# KegWasher_1_3_Schematic_EasyEDA.net
KiCad netlist of a schematic drawn in EasyEDA
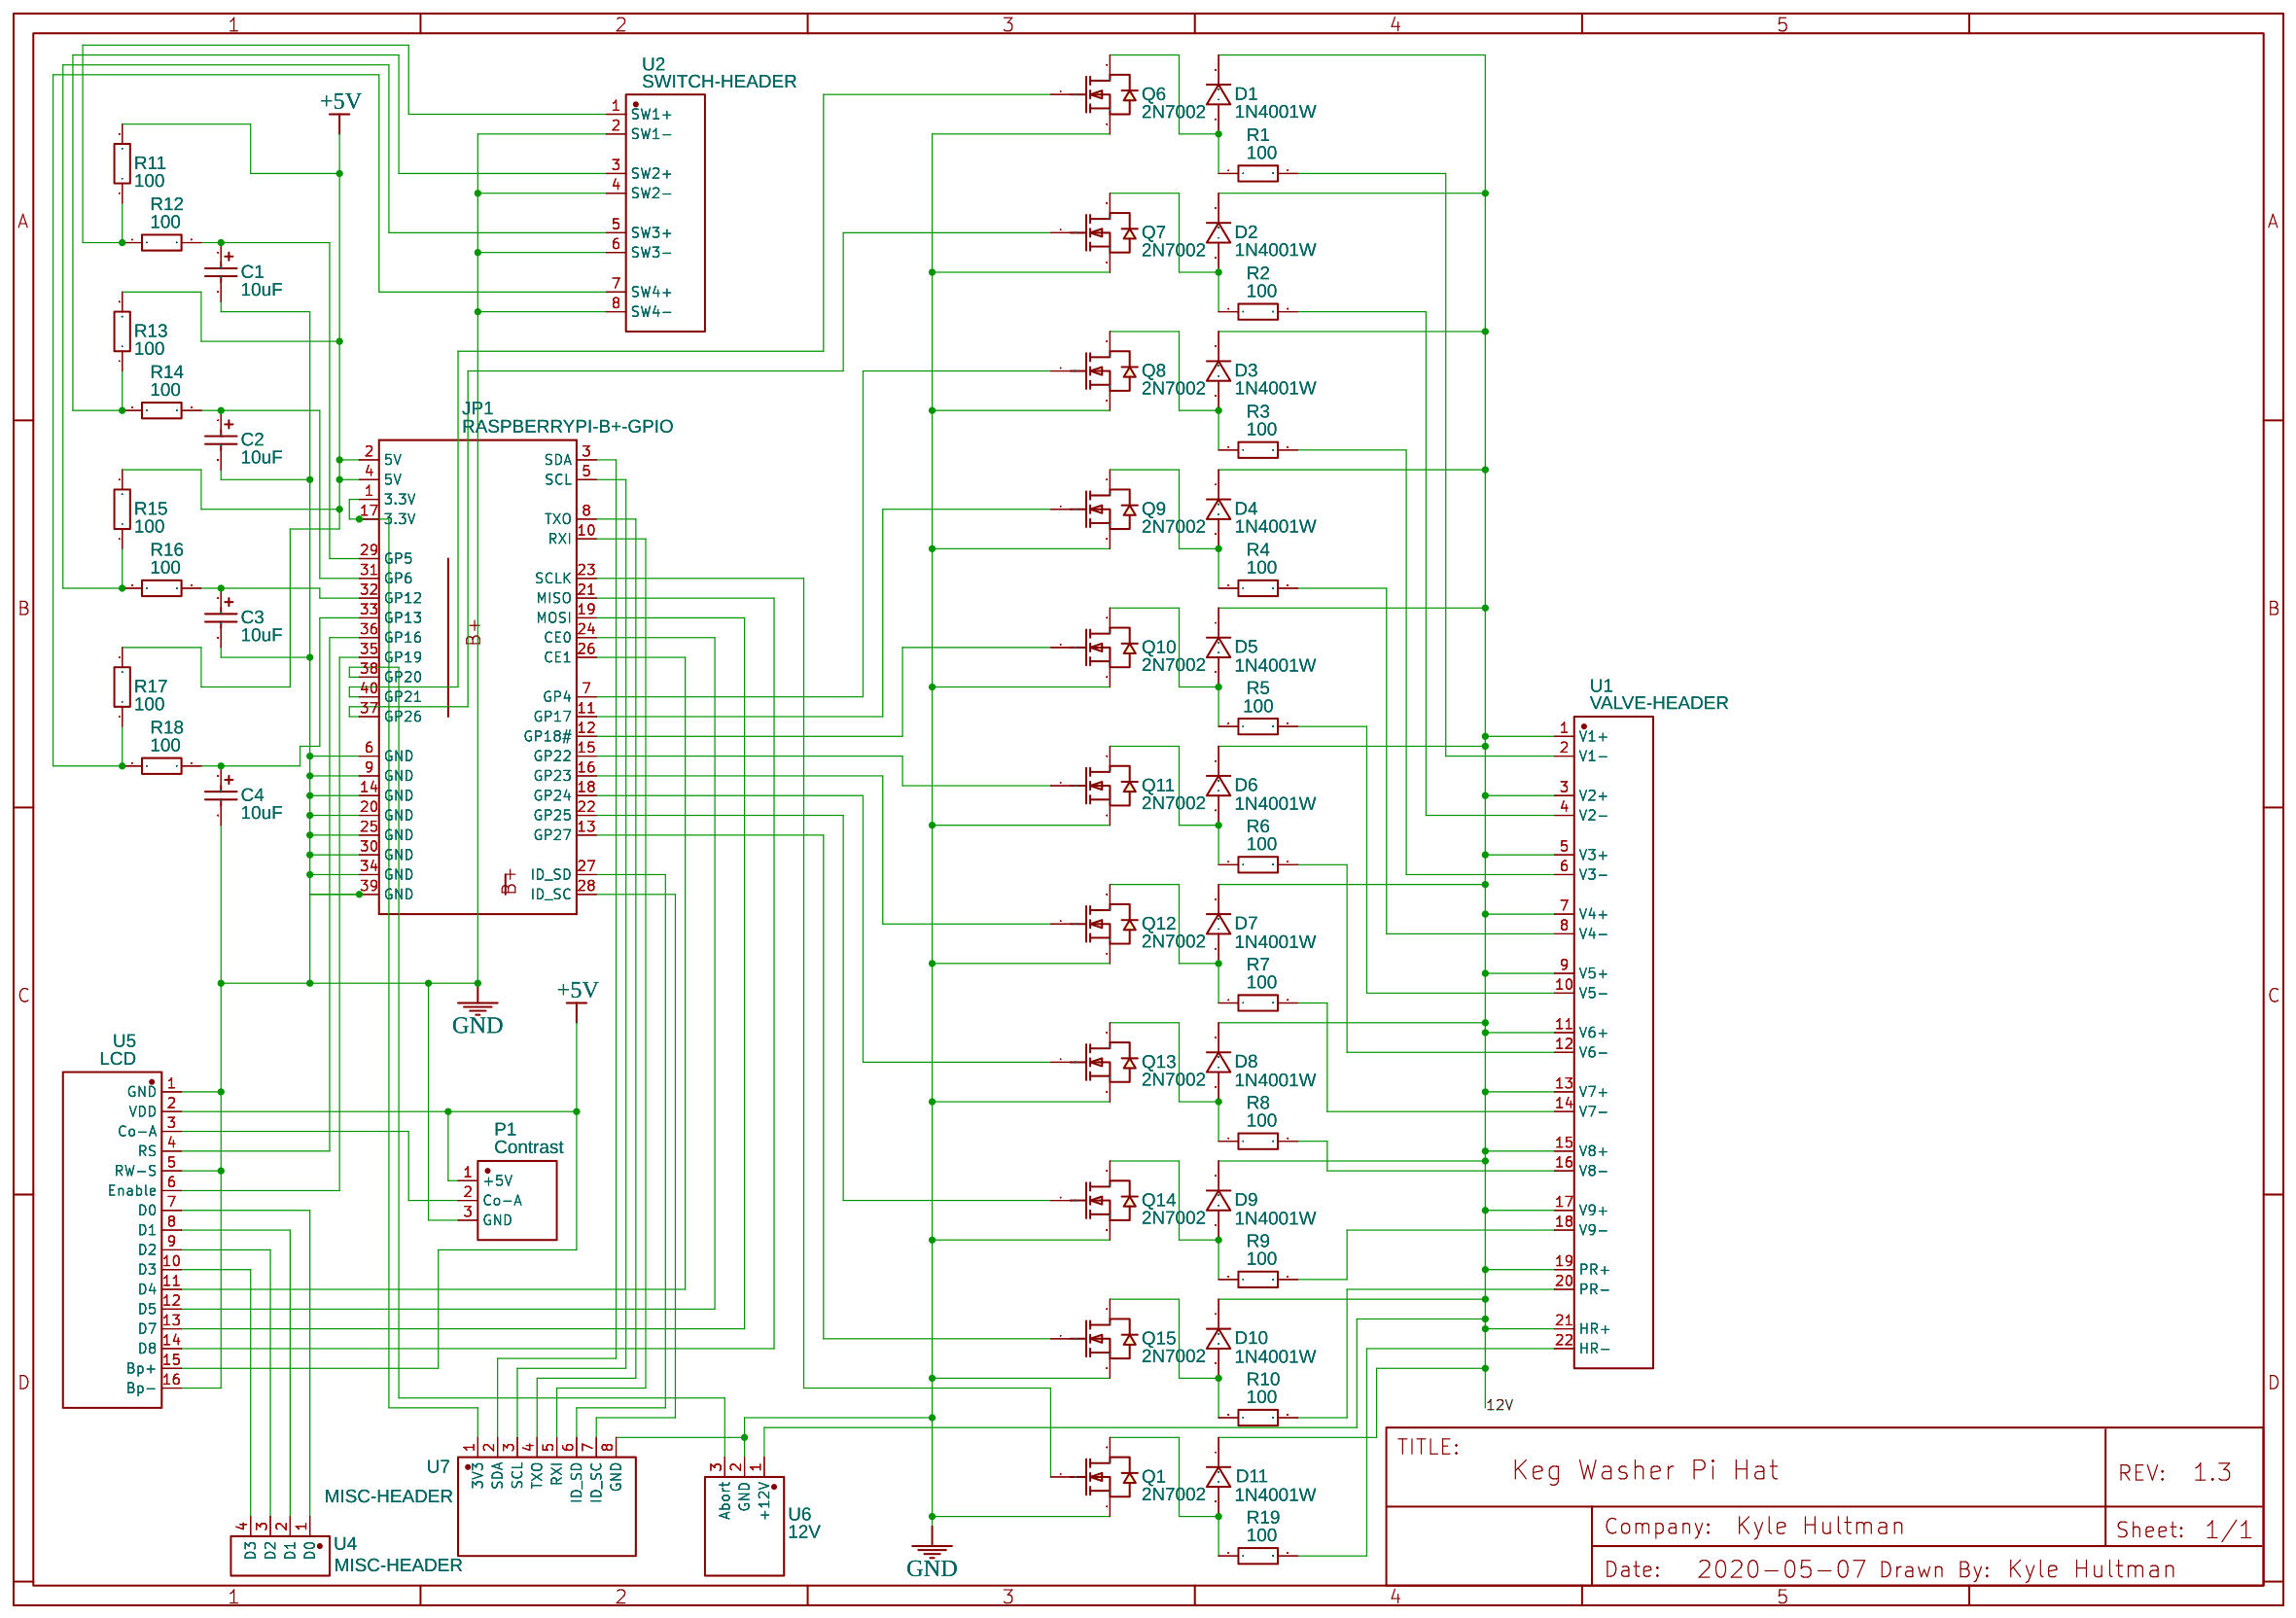
[diagram p0: schematic sheet]

(export (version "E")
  (design (tool "Eeschema 10.0.6"))
  (components
    (comp (ref "C1")
      (value "10uF")
      (fields
        (field (name "BOM_Manufacturer Part") "TAJA106K016RNJ")
        (field (name "BOM_Supplier Part") "C7171")
      )
      (libsource (lib "") (part "TAJA106K016RNJ"))
    )
    (comp (ref "C2")
      (value "10uF")
      (fields
        (field (name "BOM_Manufacturer Part") "TAJA106K016RNJ")
        (field (name "BOM_Supplier Part") "C7171")
      )
      (libsource (lib "") (part "TAJA106K016RNJ"))
    )
    (comp (ref "C3")
      (value "10uF")
      (fields
        (field (name "BOM_Manufacturer Part") "TAJA106K016RNJ")
        (field (name "BOM_Supplier Part") "C7171")
      )
      (libsource (lib "") (part "TAJA106K016RNJ"))
    )
    (comp (ref "C4")
      (value "10uF")
      (fields
        (field (name "BOM_Manufacturer Part") "TAJA106K016RNJ")
        (field (name "BOM_Supplier Part") "C7171")
      )
      (libsource (lib "") (part "TAJA106K016RNJ"))
    )
    (comp (ref "D1")
      (value "1N4001W")
      (fields (field (name "BOM_Supplier Part") "C162732"))
      (libsource (lib "") (part "1N4001W"))
    )
    (comp (ref "D2")
      (value "1N4001W")
      (fields (field (name "BOM_Supplier Part") "C162732"))
      (libsource (lib "") (part "1N4001W"))
    )
    (comp (ref "D3")
      (value "1N4001W")
      (fields (field (name "BOM_Supplier Part") "C162732"))
      (libsource (lib "") (part "1N4001W"))
    )
    (comp (ref "D4")
      (value "1N4001W")
      (fields (field (name "BOM_Supplier Part") "C162732"))
      (libsource (lib "") (part "1N4001W"))
    )
    (comp (ref "D5")
      (value "1N4001W")
      (fields (field (name "BOM_Supplier Part") "C162732"))
      (libsource (lib "") (part "1N4001W"))
    )
    (comp (ref "D6")
      (value "1N4001W")
      (fields (field (name "BOM_Supplier Part") "C162732"))
      (libsource (lib "") (part "1N4001W"))
    )
    (comp (ref "D7")
      (value "1N4001W")
      (fields (field (name "BOM_Supplier Part") "C162732"))
      (libsource (lib "") (part "1N4001W"))
    )
    (comp (ref "D8")
      (value "1N4001W")
      (fields (field (name "BOM_Supplier Part") "C162732"))
      (libsource (lib "") (part "1N4001W"))
    )
    (comp (ref "D9")
      (value "1N4001W")
      (fields (field (name "BOM_Supplier Part") "C162732"))
      (libsource (lib "") (part "1N4001W"))
    )
    (comp (ref "D10")
      (value "1N4001W")
      (fields (field (name "BOM_Supplier Part") "C162732"))
      (libsource (lib "") (part "1N4001W"))
    )
    (comp (ref "D11")
      (value "1N4001W")
      (fields (field (name "BOM_Supplier Part") "C162732"))
      (libsource (lib "") (part "1N4001W"))
    )
    (comp (ref "JP1") (value "RASPBERRYPI-B+-GPIO") (libsource (lib "") (part "RASPBERRYPI-B+-GPIO")))
    (comp (ref "P1") (value "Contrast") (libsource (lib "") (part "Contrast")))
    (comp (ref "Q1")
      (value "2N7002")
      (fields (field (name "BOM_Supplier Part") "C8545"))
      (libsource (lib "") (part "2N7002"))
    )
    (comp (ref "Q6")
      (value "2N7002")
      (fields (field (name "BOM_Supplier Part") "C8545"))
      (libsource (lib "") (part "2N7002"))
    )
    (comp (ref "Q7")
      (value "2N7002")
      (fields (field (name "BOM_Supplier Part") "C8545"))
      (libsource (lib "") (part "2N7002"))
    )
    (comp (ref "Q8")
      (value "2N7002")
      (fields (field (name "BOM_Supplier Part") "C8545"))
      (libsource (lib "") (part "2N7002"))
    )
    (comp (ref "Q9")
      (value "2N7002")
      (fields (field (name "BOM_Supplier Part") "C8545"))
      (libsource (lib "") (part "2N7002"))
    )
    (comp (ref "Q10")
      (value "2N7002")
      (fields (field (name "BOM_Supplier Part") "C8545"))
      (libsource (lib "") (part "2N7002"))
    )
    (comp (ref "Q11")
      (value "2N7002")
      (fields (field (name "BOM_Supplier Part") "C8545"))
      (libsource (lib "") (part "2N7002"))
    )
    (comp (ref "Q12")
      (value "2N7002")
      (fields (field (name "BOM_Supplier Part") "C8545"))
      (libsource (lib "") (part "2N7002"))
    )
    (comp (ref "Q13")
      (value "2N7002")
      (fields (field (name "BOM_Supplier Part") "C8545"))
      (libsource (lib "") (part "2N7002"))
    )
    (comp (ref "Q14")
      (value "2N7002")
      (fields (field (name "BOM_Supplier Part") "C8545"))
      (libsource (lib "") (part "2N7002"))
    )
    (comp (ref "Q15")
      (value "2N7002")
      (fields (field (name "BOM_Supplier Part") "C8545"))
      (libsource (lib "") (part "2N7002"))
    )
    (comp (ref "R1")
      (value "100")
      (fields
        (field (name "BOM_Manufacturer Part") "0805W8F1000T5E")
        (field (name "BOM_Supplier Part") "C17408")
      )
      (libsource (lib "") (part "0805W8F1000T5E"))
    )
    (comp (ref "R2")
      (value "100")
      (fields
        (field (name "BOM_Manufacturer Part") "0805W8F1000T5E")
        (field (name "BOM_Supplier Part") "C17408")
      )
      (libsource (lib "") (part "0805W8F1000T5E"))
    )
    (comp (ref "R3")
      (value "100")
      (fields
        (field (name "BOM_Manufacturer Part") "0805W8F1000T5E")
        (field (name "BOM_Supplier Part") "C17408")
      )
      (libsource (lib "") (part "0805W8F1000T5E"))
    )
    (comp (ref "R4")
      (value "100")
      (fields
        (field (name "BOM_Manufacturer Part") "0805W8F1000T5E")
        (field (name "BOM_Supplier Part") "C17408")
      )
      (libsource (lib "") (part "0805W8F1000T5E"))
    )
    (comp (ref "R5")
      (value "100")
      (fields
        (field (name "BOM_Manufacturer Part") "0805W8F1000T5E")
        (field (name "BOM_Supplier Part") "C17408")
      )
      (libsource (lib "") (part "0805W8F1000T5E"))
    )
    (comp (ref "R6")
      (value "100")
      (fields
        (field (name "BOM_Manufacturer Part") "0805W8F1000T5E")
        (field (name "BOM_Supplier Part") "C17408")
      )
      (libsource (lib "") (part "0805W8F1000T5E"))
    )
    (comp (ref "R7")
      (value "100")
      (fields
        (field (name "BOM_Manufacturer Part") "0805W8F1000T5E")
        (field (name "BOM_Supplier Part") "C17408")
      )
      (libsource (lib "") (part "0805W8F1000T5E"))
    )
    (comp (ref "R8")
      (value "100")
      (fields
        (field (name "BOM_Manufacturer Part") "0805W8F1000T5E")
        (field (name "BOM_Supplier Part") "C17408")
      )
      (libsource (lib "") (part "0805W8F1000T5E"))
    )
    (comp (ref "R9")
      (value "100")
      (fields
        (field (name "BOM_Manufacturer Part") "0805W8F1000T5E")
        (field (name "BOM_Supplier Part") "C17408")
      )
      (libsource (lib "") (part "0805W8F1000T5E"))
    )
    (comp (ref "R10")
      (value "100")
      (fields
        (field (name "BOM_Manufacturer Part") "0805W8F1000T5E")
        (field (name "BOM_Supplier Part") "C17408")
      )
      (libsource (lib "") (part "0805W8F1000T5E"))
    )
    (comp (ref "R11")
      (value "100")
      (fields
        (field (name "BOM_Manufacturer Part") "0805W8F1000T5E")
        (field (name "BOM_Supplier Part") "C17408")
      )
      (libsource (lib "") (part "0805W8F1000T5E_1"))
    )
    (comp (ref "R12")
      (value "100")
      (fields
        (field (name "BOM_Manufacturer Part") "0805W8F1000T5E")
        (field (name "BOM_Supplier Part") "C17408")
      )
      (libsource (lib "") (part "0805W8F1000T5E"))
    )
    (comp (ref "R13")
      (value "100")
      (fields
        (field (name "BOM_Manufacturer Part") "0805W8F1000T5E")
        (field (name "BOM_Supplier Part") "C17408")
      )
      (libsource (lib "") (part "0805W8F1000T5E_1"))
    )
    (comp (ref "R14")
      (value "100")
      (fields
        (field (name "BOM_Manufacturer Part") "0805W8F1000T5E")
        (field (name "BOM_Supplier Part") "C17408")
      )
      (libsource (lib "") (part "0805W8F1000T5E"))
    )
    (comp (ref "R15")
      (value "100")
      (fields
        (field (name "BOM_Manufacturer Part") "0805W8F1000T5E")
        (field (name "BOM_Supplier Part") "C17408")
      )
      (libsource (lib "") (part "0805W8F1000T5E_1"))
    )
    (comp (ref "R16")
      (value "100")
      (fields
        (field (name "BOM_Manufacturer Part") "0805W8F1000T5E")
        (field (name "BOM_Supplier Part") "C17408")
      )
      (libsource (lib "") (part "0805W8F1000T5E"))
    )
    (comp (ref "R17")
      (value "100")
      (fields
        (field (name "BOM_Manufacturer Part") "0805W8F1000T5E")
        (field (name "BOM_Supplier Part") "C17408")
      )
      (libsource (lib "") (part "0805W8F1000T5E_1"))
    )
    (comp (ref "R18")
      (value "100")
      (fields
        (field (name "BOM_Manufacturer Part") "0805W8F1000T5E")
        (field (name "BOM_Supplier Part") "C17408")
      )
      (libsource (lib "") (part "0805W8F1000T5E"))
    )
    (comp (ref "R19")
      (value "100")
      (fields
        (field (name "BOM_Manufacturer Part") "0805W8F1000T5E")
        (field (name "BOM_Supplier Part") "C17408")
      )
      (libsource (lib "") (part "0805W8F1000T5E"))
    )
    (comp (ref "U1") (value "VALVE-HEADER") (libsource (lib "") (part "VALVE-HEADER")))
    (comp (ref "U2") (value "SWITCH-HEADER") (libsource (lib "") (part "SWITCH-HEADER")))
    (comp (ref "U4") (value "MISC-HEADER") (libsource (lib "") (part "MISC-HEADER_1")))
    (comp (ref "U5") (value "LCD") (libsource (lib "") (part "LCD")))
    (comp (ref "U6") (value "12V") (libsource (lib "") (part "12V")))
    (comp (ref "U7") (value "MISC-HEADER") (libsource (lib "") (part "MISC-HEADER")))
  )
  (nets
    (net (code "1") (name "+5V") (class "Default")
      (node (ref "JP1") (pin "2") (pinfunction "5V_2") (pintype "passive"))
      (node (ref "JP1") (pin "4") (pinfunction "5V_4") (pintype "passive"))
      (node (ref "P1") (pin "1") (pinfunction "+5V_1") (pintype "unspecified"))
      (node (ref "R11") (pin "2") (pinfunction "2_2") (pintype "input"))
      (node (ref "R13") (pin "2") (pinfunction "2_2") (pintype "input"))
      (node (ref "R15") (pin "2") (pinfunction "2_2") (pintype "input"))
      (node (ref "R17") (pin "2") (pinfunction "2_2") (pintype "input"))
      (node (ref "U5") (pin "15") (pinfunction "Bp+_15") (pintype "unspecified"))
      (node (ref "U5") (pin "2") (pinfunction "VDD_2") (pintype "unspecified"))
    )
    (net (code "2") (name "/12V") (class "Default")
      (node (ref "D1") (pin "1") (pinfunction "C_1") (pintype "unspecified"))
      (node (ref "D10") (pin "1") (pinfunction "C_1") (pintype "unspecified"))
      (node (ref "D11") (pin "1") (pinfunction "C_1") (pintype "unspecified"))
      (node (ref "D2") (pin "1") (pinfunction "C_1") (pintype "unspecified"))
      (node (ref "D3") (pin "1") (pinfunction "C_1") (pintype "unspecified"))
      (node (ref "D4") (pin "1") (pinfunction "C_1") (pintype "unspecified"))
      (node (ref "D5") (pin "1") (pinfunction "C_1") (pintype "unspecified"))
      (node (ref "D6") (pin "1") (pinfunction "C_1") (pintype "unspecified"))
      (node (ref "D7") (pin "1") (pinfunction "C_1") (pintype "unspecified"))
      (node (ref "D8") (pin "1") (pinfunction "C_1") (pintype "unspecified"))
      (node (ref "D9") (pin "1") (pinfunction "C_1") (pintype "unspecified"))
      (node (ref "U1") (pin "1") (pinfunction "V1+_1") (pintype "unspecified"))
      (node (ref "U1") (pin "11") (pinfunction "V6+_11") (pintype "unspecified"))
      (node (ref "U1") (pin "13") (pinfunction "V7+_13") (pintype "unspecified"))
      (node (ref "U1") (pin "15") (pinfunction "V8+_15") (pintype "unspecified"))
      (node (ref "U1") (pin "17") (pinfunction "V9+_17") (pintype "unspecified"))
      (node (ref "U1") (pin "19") (pinfunction "PR+_19") (pintype "unspecified"))
      (node (ref "U1") (pin "21") (pinfunction "HR+_21") (pintype "unspecified"))
      (node (ref "U1") (pin "3") (pinfunction "V2+_3") (pintype "unspecified"))
      (node (ref "U1") (pin "5") (pinfunction "V3+_5") (pintype "unspecified"))
      (node (ref "U1") (pin "7") (pinfunction "V4+_7") (pintype "unspecified"))
      (node (ref "U1") (pin "9") (pinfunction "V5+_9") (pintype "unspecified"))
      (node (ref "U6") (pin "1") (pinfunction "+12V_1") (pintype "unspecified"))
    )
    (net (code "3") (name "GND") (class "Default")
      (node (ref "C1") (pin "2") (pinfunction "2_2") (pintype "input"))
      (node (ref "C2") (pin "2") (pinfunction "2_2") (pintype "input"))
      (node (ref "C3") (pin "2") (pinfunction "2_2") (pintype "input"))
      (node (ref "C4") (pin "2") (pinfunction "2_2") (pintype "input"))
      (node (ref "JP1") (pin "14") (pinfunction "GND_14") (pintype "passive"))
      (node (ref "JP1") (pin "20") (pinfunction "GND_20") (pintype "passive"))
      (node (ref "JP1") (pin "25") (pinfunction "GND_25") (pintype "passive"))
      (node (ref "JP1") (pin "30") (pinfunction "GND_30") (pintype "passive"))
      (node (ref "JP1") (pin "34") (pinfunction "GND_34") (pintype "passive"))
      (node (ref "JP1") (pin "39") (pinfunction "GND_39") (pintype "passive"))
      (node (ref "JP1") (pin "6") (pinfunction "GND_6") (pintype "passive"))
      (node (ref "JP1") (pin "9") (pinfunction "GND_9") (pintype "passive"))
      (node (ref "P1") (pin "3") (pinfunction "GND_3") (pintype "unspecified"))
      (node (ref "Q1") (pin "2") (pinfunction "S_2") (pintype "unspecified"))
      (node (ref "Q10") (pin "2") (pinfunction "S_2") (pintype "unspecified"))
      (node (ref "Q11") (pin "2") (pinfunction "S_2") (pintype "unspecified"))
      (node (ref "Q12") (pin "2") (pinfunction "S_2") (pintype "unspecified"))
      (node (ref "Q13") (pin "2") (pinfunction "S_2") (pintype "unspecified"))
      (node (ref "Q14") (pin "2") (pinfunction "S_2") (pintype "unspecified"))
      (node (ref "Q15") (pin "2") (pinfunction "S_2") (pintype "unspecified"))
      (node (ref "Q6") (pin "2") (pinfunction "S_2") (pintype "unspecified"))
      (node (ref "Q7") (pin "2") (pinfunction "S_2") (pintype "unspecified"))
      (node (ref "Q8") (pin "2") (pinfunction "S_2") (pintype "unspecified"))
      (node (ref "Q9") (pin "2") (pinfunction "S_2") (pintype "unspecified"))
      (node (ref "U2") (pin "2") (pinfunction "SW1-_2") (pintype "unspecified"))
      (node (ref "U2") (pin "4") (pinfunction "SW2-_4") (pintype "unspecified"))
      (node (ref "U2") (pin "6") (pinfunction "SW3-_6") (pintype "unspecified"))
      (node (ref "U2") (pin "8") (pinfunction "SW4-_8") (pintype "unspecified"))
      (node (ref "U5") (pin "1") (pinfunction "GND_1") (pintype "unspecified"))
      (node (ref "U5") (pin "16") (pinfunction "Bp-_16") (pintype "unspecified"))
      (node (ref "U5") (pin "5") (pinfunction "RW-S_5") (pintype "unspecified"))
      (node (ref "U6") (pin "2") (pinfunction "GND_2") (pintype "unspecified"))
      (node (ref "U7") (pin "8") (pinfunction "GND_8") (pintype "unspecified"))
    )
    (net (code "4") (name "Net-(D1-A)") (class "Default")
      (node (ref "D1") (pin "2") (pinfunction "A_2") (pintype "unspecified"))
      (node (ref "Q6") (pin "3") (pinfunction "D_3") (pintype "unspecified"))
      (node (ref "R1") (pin "1") (pinfunction "1_1") (pintype "input"))
    )
    (net (code "5") (name "Net-(D2-A)") (class "Default")
      (node (ref "D2") (pin "2") (pinfunction "A_2") (pintype "unspecified"))
      (node (ref "Q7") (pin "3") (pinfunction "D_3") (pintype "unspecified"))
      (node (ref "R2") (pin "1") (pinfunction "1_1") (pintype "input"))
    )
    (net (code "6") (name "Net-(D3-A)") (class "Default")
      (node (ref "D3") (pin "2") (pinfunction "A_2") (pintype "unspecified"))
      (node (ref "Q8") (pin "3") (pinfunction "D_3") (pintype "unspecified"))
      (node (ref "R3") (pin "1") (pinfunction "1_1") (pintype "input"))
    )
    (net (code "7") (name "Net-(D4-A)") (class "Default")
      (node (ref "D4") (pin "2") (pinfunction "A_2") (pintype "unspecified"))
      (node (ref "Q9") (pin "3") (pinfunction "D_3") (pintype "unspecified"))
      (node (ref "R4") (pin "1") (pinfunction "1_1") (pintype "input"))
    )
    (net (code "8") (name "Net-(D5-A)") (class "Default")
      (node (ref "D5") (pin "2") (pinfunction "A_2") (pintype "unspecified"))
      (node (ref "Q10") (pin "3") (pinfunction "D_3") (pintype "unspecified"))
      (node (ref "R5") (pin "1") (pinfunction "1_1") (pintype "input"))
    )
    (net (code "9") (name "Net-(D6-A)") (class "Default")
      (node (ref "D6") (pin "2") (pinfunction "A_2") (pintype "unspecified"))
      (node (ref "Q11") (pin "3") (pinfunction "D_3") (pintype "unspecified"))
      (node (ref "R6") (pin "1") (pinfunction "1_1") (pintype "input"))
    )
    (net (code "10") (name "Net-(D7-A)") (class "Default")
      (node (ref "D7") (pin "2") (pinfunction "A_2") (pintype "unspecified"))
      (node (ref "Q12") (pin "3") (pinfunction "D_3") (pintype "unspecified"))
      (node (ref "R7") (pin "1") (pinfunction "1_1") (pintype "input"))
    )
    (net (code "11") (name "Net-(D8-A)") (class "Default")
      (node (ref "D8") (pin "2") (pinfunction "A_2") (pintype "unspecified"))
      (node (ref "Q13") (pin "3") (pinfunction "D_3") (pintype "unspecified"))
      (node (ref "R8") (pin "1") (pinfunction "1_1") (pintype "input"))
    )
    (net (code "12") (name "Net-(D9-A)") (class "Default")
      (node (ref "D9") (pin "2") (pinfunction "A_2") (pintype "unspecified"))
      (node (ref "Q14") (pin "3") (pinfunction "D_3") (pintype "unspecified"))
      (node (ref "R9") (pin "1") (pinfunction "1_1") (pintype "input"))
    )
    (net (code "13") (name "Net-(D10-A)") (class "Default")
      (node (ref "D10") (pin "2") (pinfunction "A_2") (pintype "unspecified"))
      (node (ref "Q15") (pin "3") (pinfunction "D_3") (pintype "unspecified"))
      (node (ref "R10") (pin "1") (pinfunction "1_1") (pintype "input"))
    )
    (net (code "14") (name "Net-(D11-A)") (class "Default")
      (node (ref "D11") (pin "2") (pinfunction "A_2") (pintype "unspecified"))
      (node (ref "Q1") (pin "3") (pinfunction "D_3") (pintype "unspecified"))
      (node (ref "R19") (pin "1") (pinfunction "1_1") (pintype "input"))
    )
    (net (code "15") (name "Net-(JP1-CE0)") (class "Default")
      (node (ref "JP1") (pin "24") (pinfunction "CE0_24") (pintype "output"))
      (node (ref "U5") (pin "12") (pinfunction "D5_12") (pintype "unspecified"))
    )
    (net (code "16") (name "Net-(JP1-CE1)") (class "Default")
      (node (ref "JP1") (pin "26") (pinfunction "CE1_26") (pintype "output"))
      (node (ref "U5") (pin "11") (pinfunction "D4_11") (pintype "unspecified"))
    )
    (net (code "17") (name "Net-(JP1-GP4)") (class "Default")
      (node (ref "JP1") (pin "7") (pinfunction "GP4_7") (pintype "unspecified"))
      (node (ref "Q8") (pin "1") (pinfunction "G_1") (pintype "unspecified"))
    )
    (net (code "18") (name "Net-(JP1-GP5)") (class "Default")
      (node (ref "C1") (pin "1") (pinfunction "1_1") (pintype "input"))
      (node (ref "JP1") (pin "29") (pinfunction "GP5_29") (pintype "unspecified"))
      (node (ref "R12") (pin "2") (pinfunction "2_2") (pintype "input"))
    )
    (net (code "19") (name "Net-(JP1-GP6)") (class "Default")
      (node (ref "C2") (pin "1") (pinfunction "1_1") (pintype "input"))
      (node (ref "JP1") (pin "31") (pinfunction "GP6_31") (pintype "unspecified"))
      (node (ref "R14") (pin "2") (pinfunction "2_2") (pintype "input"))
    )
    (net (code "20") (name "Net-(JP1-GP12)") (class "Default")
      (node (ref "C3") (pin "1") (pinfunction "1_1") (pintype "input"))
      (node (ref "JP1") (pin "32") (pinfunction "GP12_32") (pintype "unspecified"))
      (node (ref "R16") (pin "2") (pinfunction "2_2") (pintype "input"))
    )
    (net (code "21") (name "Net-(JP1-GP13)") (class "Default")
      (node (ref "C4") (pin "1") (pinfunction "1_1") (pintype "input"))
      (node (ref "JP1") (pin "33") (pinfunction "GP13_33") (pintype "unspecified"))
      (node (ref "R18") (pin "2") (pinfunction "2_2") (pintype "input"))
    )
    (net (code "22") (name "Net-(JP1-GP16)") (class "Default")
      (node (ref "JP1") (pin "36") (pinfunction "GP16_36") (pintype "unspecified"))
      (node (ref "U5") (pin "4") (pinfunction "RS_4") (pintype "unspecified"))
    )
    (net (code "23") (name "Net-(JP1-GP17)") (class "Default")
      (node (ref "JP1") (pin "11") (pinfunction "GP17_11") (pintype "unspecified"))
      (node (ref "Q9") (pin "1") (pinfunction "G_1") (pintype "unspecified"))
    )
    (net (code "24") (name "Net-(JP1-GP18#)") (class "Default")
      (node (ref "JP1") (pin "12") (pinfunction "GP18#_12") (pintype "unspecified"))
      (node (ref "Q10") (pin "1") (pinfunction "G_1") (pintype "unspecified"))
    )
    (net (code "25") (name "Net-(JP1-GP19)") (class "Default")
      (node (ref "JP1") (pin "35") (pinfunction "GP19_35") (pintype "unspecified"))
      (node (ref "U5") (pin "6") (pinfunction "Enable_6") (pintype "unspecified"))
    )
    (net (code "26") (name "Net-(JP1-GP20)") (class "Default")
      (node (ref "JP1") (pin "38") (pinfunction "GP20_38") (pintype "unspecified"))
      (node (ref "U6") (pin "3") (pinfunction "Abort_3") (pintype "unspecified"))
    )
    (net (code "27") (name "Net-(JP1-GP21)") (class "Default")
      (node (ref "JP1") (pin "40") (pinfunction "GP21_40") (pintype "unspecified"))
      (node (ref "Q6") (pin "1") (pinfunction "G_1") (pintype "unspecified"))
    )
    (net (code "28") (name "Net-(JP1-GP22)") (class "Default")
      (node (ref "JP1") (pin "15") (pinfunction "GP22_15") (pintype "unspecified"))
      (node (ref "Q11") (pin "1") (pinfunction "G_1") (pintype "unspecified"))
    )
    (net (code "29") (name "Net-(JP1-GP23)") (class "Default")
      (node (ref "JP1") (pin "16") (pinfunction "GP23_16") (pintype "unspecified"))
      (node (ref "Q12") (pin "1") (pinfunction "G_1") (pintype "unspecified"))
    )
    (net (code "30") (name "Net-(JP1-GP24)") (class "Default")
      (node (ref "JP1") (pin "18") (pinfunction "GP24_18") (pintype "unspecified"))
      (node (ref "Q13") (pin "1") (pinfunction "G_1") (pintype "unspecified"))
    )
    (net (code "31") (name "Net-(JP1-GP25)") (class "Default")
      (node (ref "JP1") (pin "22") (pinfunction "GP25_22") (pintype "unspecified"))
      (node (ref "Q14") (pin "1") (pinfunction "G_1") (pintype "unspecified"))
    )
    (net (code "32") (name "Net-(JP1-GP26)") (class "Default")
      (node (ref "JP1") (pin "37") (pinfunction "GP26_37") (pintype "unspecified"))
      (node (ref "Q7") (pin "1") (pinfunction "G_1") (pintype "unspecified"))
    )
    (net (code "33") (name "Net-(JP1-GP27)") (class "Default")
      (node (ref "JP1") (pin "13") (pinfunction "GP27_13") (pintype "unspecified"))
      (node (ref "Q15") (pin "1") (pinfunction "G_1") (pintype "unspecified"))
    )
    (net (code "34") (name "Net-(JP1-ID_SC)") (class "Default")
      (node (ref "JP1") (pin "28") (pinfunction "ID_SC_28") (pintype "unspecified"))
      (node (ref "U7") (pin "7") (pinfunction "ID_SC_7") (pintype "unspecified"))
    )
    (net (code "35") (name "Net-(JP1-ID_SD)") (class "Default")
      (node (ref "JP1") (pin "27") (pinfunction "ID_SD_27") (pintype "unspecified"))
      (node (ref "U7") (pin "6") (pinfunction "ID_SD_6") (pintype "unspecified"))
    )
    (net (code "36") (name "Net-(JP1-MISO)") (class "Default")
      (node (ref "JP1") (pin "21") (pinfunction "MISO_21") (pintype "input"))
      (node (ref "U5") (pin "14") (pinfunction "D8_14") (pintype "unspecified"))
    )
    (net (code "37") (name "Net-(JP1-MOSI)") (class "Default")
      (node (ref "JP1") (pin "19") (pinfunction "MOSI_19") (pintype "output"))
      (node (ref "U5") (pin "13") (pinfunction "D7_13") (pintype "unspecified"))
    )
    (net (code "38") (name "Net-(JP1-RXI)") (class "Default")
      (node (ref "JP1") (pin "10") (pinfunction "RXI_10") (pintype "input"))
      (node (ref "U7") (pin "5") (pinfunction "RXI_5") (pintype "unspecified"))
    )
    (net (code "39") (name "Net-(JP1-SCL)") (class "Default")
      (node (ref "JP1") (pin "5") (pinfunction "SCL_5") (pintype "unspecified"))
      (node (ref "U7") (pin "3") (pinfunction "SCL_3") (pintype "unspecified"))
    )
    (net (code "40") (name "Net-(JP1-SCLK)") (class "Default")
      (node (ref "JP1") (pin "23") (pinfunction "SCLK_23") (pintype "output"))
      (node (ref "Q1") (pin "1") (pinfunction "G_1") (pintype "unspecified"))
    )
    (net (code "41") (name "Net-(JP1-SDA)") (class "Default")
      (node (ref "JP1") (pin "3") (pinfunction "SDA_3") (pintype "unspecified"))
      (node (ref "U7") (pin "2") (pinfunction "SDA_2") (pintype "unspecified"))
    )
    (net (code "42") (name "Net-(JP1-TXO)") (class "Default")
      (node (ref "JP1") (pin "8") (pinfunction "TXO_8") (pintype "output"))
      (node (ref "U7") (pin "4") (pinfunction "TXO_4") (pintype "unspecified"))
    )
    (net (code "43") (name "Net-(P1-Co-A)") (class "Default")
      (node (ref "P1") (pin "2") (pinfunction "Co-A_2") (pintype "unspecified"))
      (node (ref "U5") (pin "3") (pinfunction "Co-A_3") (pintype "unspecified"))
    )
    (net (code "44") (name "Net-(U1-HR-)") (class "Default")
      (node (ref "R19") (pin "2") (pinfunction "2_2") (pintype "input"))
      (node (ref "U1") (pin "22") (pinfunction "HR-_22") (pintype "unspecified"))
    )
    (net (code "45") (name "Net-(U1-PR-)") (class "Default")
      (node (ref "R10") (pin "2") (pinfunction "2_2") (pintype "input"))
      (node (ref "U1") (pin "20") (pinfunction "PR-_20") (pintype "unspecified"))
    )
    (net (code "46") (name "Net-(U1-V1-)") (class "Default")
      (node (ref "R1") (pin "2") (pinfunction "2_2") (pintype "input"))
      (node (ref "U1") (pin "2") (pinfunction "V1-_2") (pintype "unspecified"))
    )
    (net (code "47") (name "Net-(U1-V2-)") (class "Default")
      (node (ref "R2") (pin "2") (pinfunction "2_2") (pintype "input"))
      (node (ref "U1") (pin "4") (pinfunction "V2-_4") (pintype "unspecified"))
    )
    (net (code "48") (name "Net-(U1-V3-)") (class "Default")
      (node (ref "R3") (pin "2") (pinfunction "2_2") (pintype "input"))
      (node (ref "U1") (pin "6") (pinfunction "V3-_6") (pintype "unspecified"))
    )
    (net (code "49") (name "Net-(U1-V4-)") (class "Default")
      (node (ref "R4") (pin "2") (pinfunction "2_2") (pintype "input"))
      (node (ref "U1") (pin "8") (pinfunction "V4-_8") (pintype "unspecified"))
    )
    (net (code "50") (name "Net-(U1-V5-)") (class "Default")
      (node (ref "R5") (pin "2") (pinfunction "2_2") (pintype "input"))
      (node (ref "U1") (pin "10") (pinfunction "V5-_10") (pintype "unspecified"))
    )
    (net (code "51") (name "Net-(U1-V6-)") (class "Default")
      (node (ref "R6") (pin "2") (pinfunction "2_2") (pintype "input"))
      (node (ref "U1") (pin "12") (pinfunction "V6-_12") (pintype "unspecified"))
    )
    (net (code "52") (name "Net-(U1-V7-)") (class "Default")
      (node (ref "R7") (pin "2") (pinfunction "2_2") (pintype "input"))
      (node (ref "U1") (pin "14") (pinfunction "V7-_14") (pintype "unspecified"))
    )
    (net (code "53") (name "Net-(U1-V8-)") (class "Default")
      (node (ref "R8") (pin "2") (pinfunction "2_2") (pintype "input"))
      (node (ref "U1") (pin "16") (pinfunction "V8-_16") (pintype "unspecified"))
    )
    (net (code "54") (name "Net-(U1-V9-)") (class "Default")
      (node (ref "R9") (pin "2") (pinfunction "2_2") (pintype "input"))
      (node (ref "U1") (pin "18") (pinfunction "V9-_18") (pintype "unspecified"))
    )
    (net (code "55") (name "Net-(U2-SW1+)") (class "Default")
      (node (ref "R11") (pin "1") (pinfunction "1_1") (pintype "input"))
      (node (ref "R12") (pin "1") (pinfunction "1_1") (pintype "input"))
      (node (ref "U2") (pin "1") (pinfunction "SW1+_1") (pintype "unspecified"))
    )
    (net (code "56") (name "Net-(U2-SW2+)") (class "Default")
      (node (ref "R13") (pin "1") (pinfunction "1_1") (pintype "input"))
      (node (ref "R14") (pin "1") (pinfunction "1_1") (pintype "input"))
      (node (ref "U2") (pin "3") (pinfunction "SW2+_3") (pintype "unspecified"))
    )
    (net (code "57") (name "Net-(U2-SW3+)") (class "Default")
      (node (ref "R15") (pin "1") (pinfunction "1_1") (pintype "input"))
      (node (ref "R16") (pin "1") (pinfunction "1_1") (pintype "input"))
      (node (ref "U2") (pin "5") (pinfunction "SW3+_5") (pintype "unspecified"))
    )
    (net (code "58") (name "Net-(U2-SW4+)") (class "Default")
      (node (ref "R17") (pin "1") (pinfunction "1_1") (pintype "input"))
      (node (ref "R18") (pin "1") (pinfunction "1_1") (pintype "input"))
      (node (ref "U2") (pin "7") (pinfunction "SW4+_7") (pintype "unspecified"))
    )
    (net (code "59") (name "Net-(U4-D0)") (class "Default")
      (node (ref "U4") (pin "1") (pinfunction "D0_1") (pintype "unspecified"))
      (node (ref "U5") (pin "7") (pinfunction "D0_7") (pintype "unspecified"))
    )
    (net (code "60") (name "Net-(U4-D1)") (class "Default")
      (node (ref "U4") (pin "2") (pinfunction "D1_2") (pintype "unspecified"))
      (node (ref "U5") (pin "8") (pinfunction "D1_8") (pintype "unspecified"))
    )
    (net (code "61") (name "Net-(U4-D2)") (class "Default")
      (node (ref "U4") (pin "3") (pinfunction "D2_3") (pintype "unspecified"))
      (node (ref "U5") (pin "9") (pinfunction "D2_9") (pintype "unspecified"))
    )
    (net (code "62") (name "Net-(U4-D3)") (class "Default")
      (node (ref "U4") (pin "4") (pinfunction "D3_4") (pintype "unspecified"))
      (node (ref "U5") (pin "10") (pinfunction "D3_10") (pintype "unspecified"))
    )
    (net (code "63") (name "Net-(U7-3V3)") (class "Default")
      (node (ref "JP1") (pin "1") (pinfunction "3.3V_1") (pintype "passive"))
      (node (ref "JP1") (pin "17") (pinfunction "3.3V_17") (pintype "passive"))
      (node (ref "U7") (pin "1") (pinfunction "3V3_1") (pintype "unspecified"))
    )
  )
)
